# Drinks_MotorDriver-v0_2.net
KiCad netlist of a schematic drawn in EAGLE
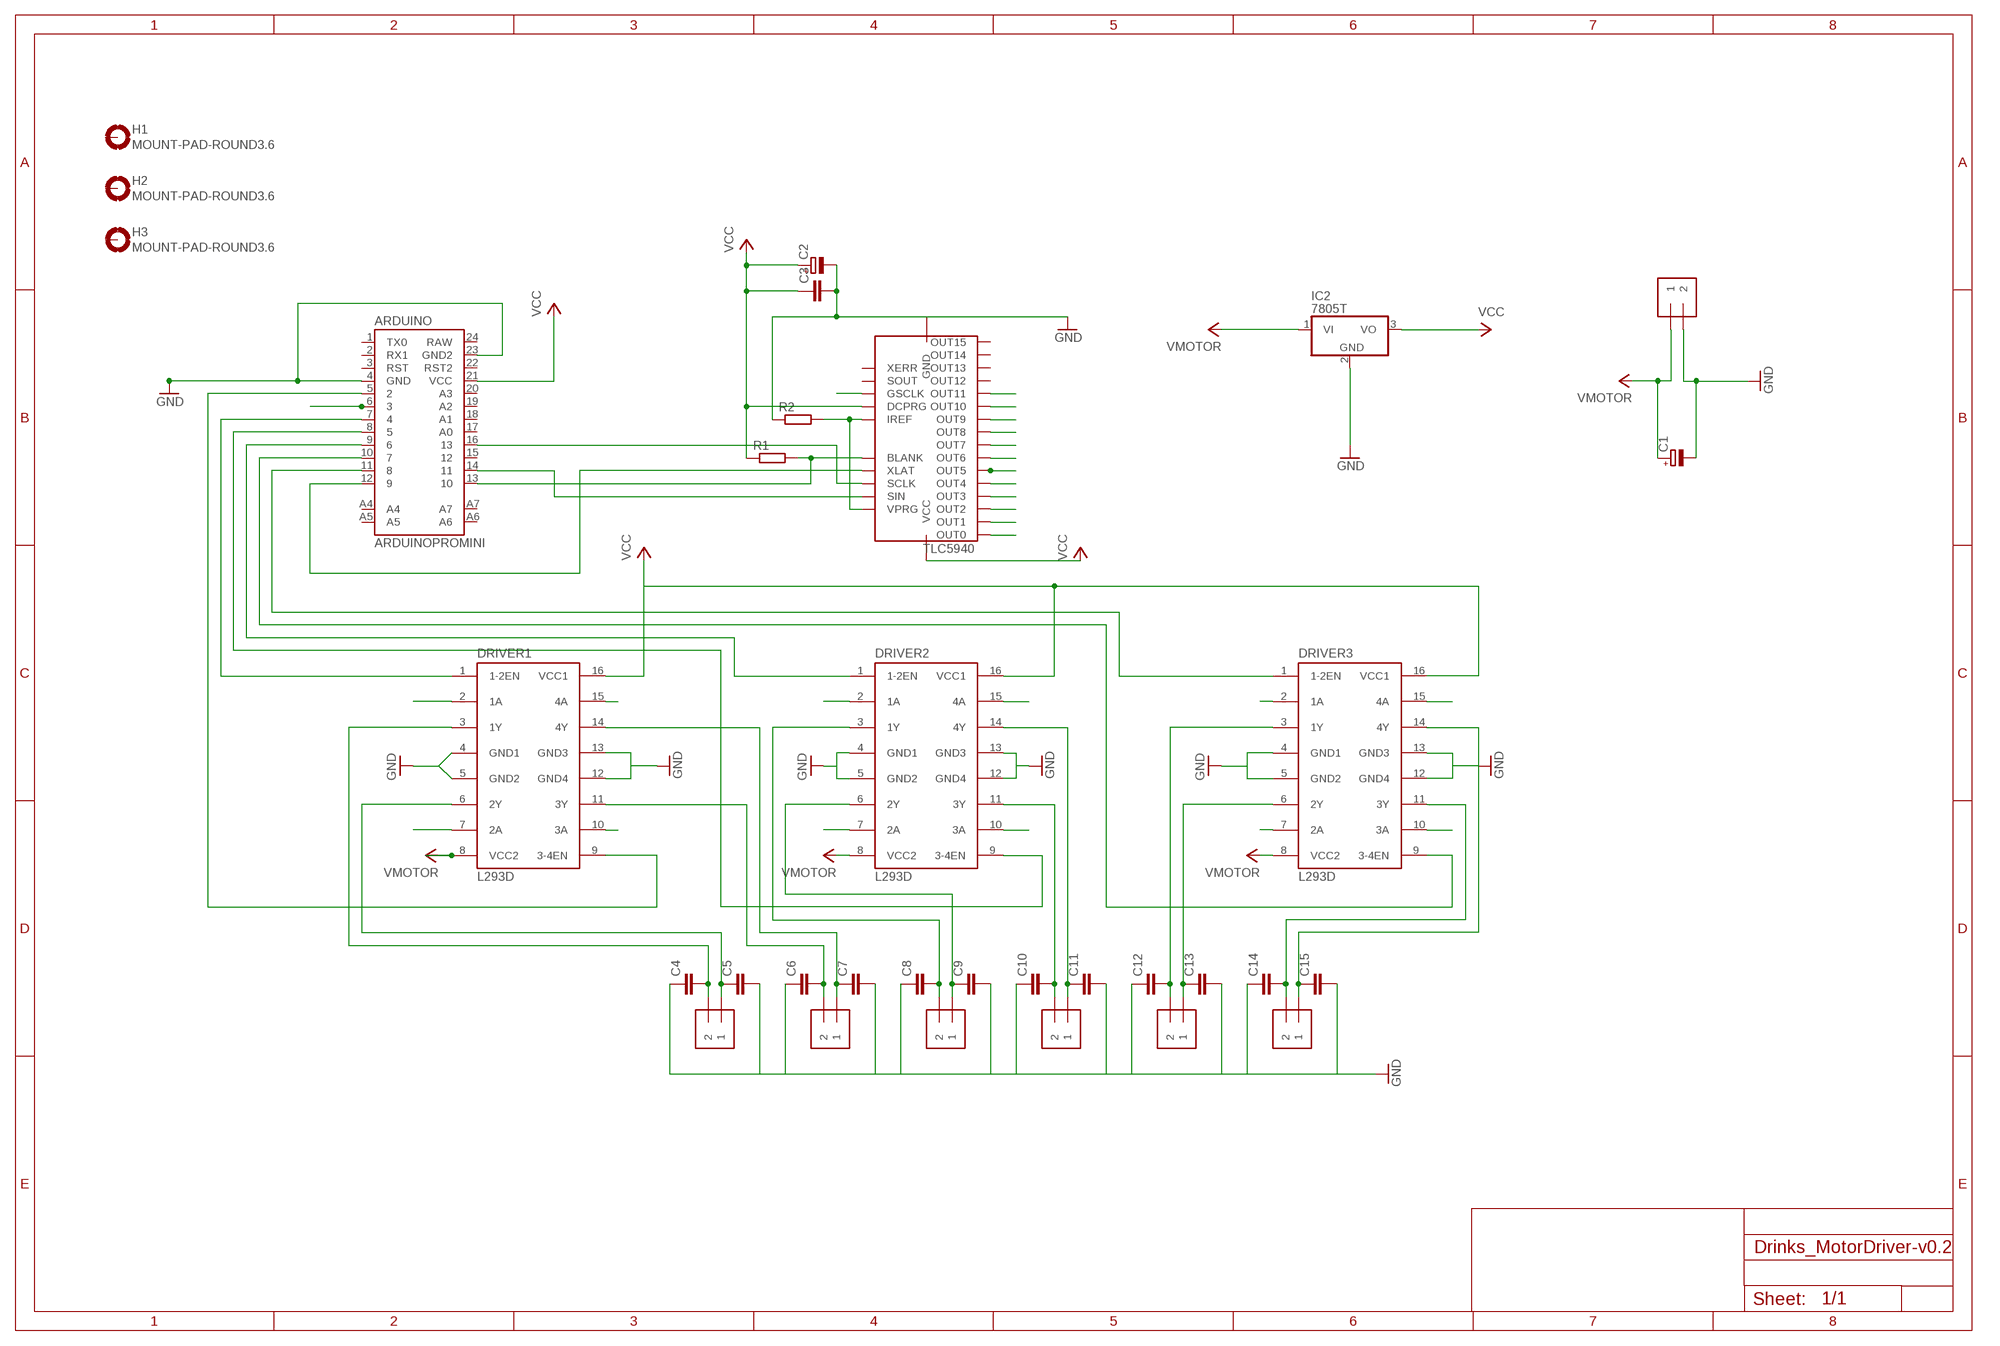
[diagram p0: schematic, sheet 1]

(export (version "E")
  (design (tool "Eeschema 10.0.6"))
  (components
    (comp (ref "ARDUINO")
      (value "ARDUINOPROMINI")
      (footprint "eagle-import:ARDUINO_PRO_MINI")
      (libsource (lib "eagle-import") (part "ARDUINO_PRO_MINI"))
    )
    (comp (ref "C1")
      (value "CPOL-EUE5-8.5")
      (footprint "eagle-import:E5-8,5")
      (libsource (lib "eagle-import") (part "CPOL-EUE5-8.5"))
    )
    (comp (ref "C2")
      (value "CPOL-EUE5-8.5")
      (footprint "eagle-import:E5-8,5")
      (libsource (lib "eagle-import") (part "CPOL-EUE5-8.5"))
    )
    (comp (ref "C3")
      (value "C-EU025-025X050")
      (footprint "eagle-import:C025-025X050")
      (libsource (lib "eagle-import") (part "C-EU025-025X050"))
    )
    (comp (ref "C4")
      (value "C-EU025-025X050")
      (footprint "eagle-import:C025-025X050")
      (libsource (lib "eagle-import") (part "C-EU025-025X050"))
    )
    (comp (ref "C5")
      (value "C-EU025-025X050")
      (footprint "eagle-import:C025-025X050")
      (libsource (lib "eagle-import") (part "C-EU025-025X050"))
    )
    (comp (ref "C6")
      (value "C-EU025-025X050")
      (footprint "eagle-import:C025-025X050")
      (libsource (lib "eagle-import") (part "C-EU025-025X050"))
    )
    (comp (ref "C7")
      (value "C-EU025-025X050")
      (footprint "eagle-import:C025-025X050")
      (libsource (lib "eagle-import") (part "C-EU025-025X050"))
    )
    (comp (ref "C8")
      (value "C-EU025-025X050")
      (footprint "eagle-import:C025-025X050")
      (libsource (lib "eagle-import") (part "C-EU025-025X050"))
    )
    (comp (ref "C9")
      (value "C-EU025-025X050")
      (footprint "eagle-import:C025-025X050")
      (libsource (lib "eagle-import") (part "C-EU025-025X050"))
    )
    (comp (ref "C10")
      (value "C-EU025-025X050")
      (footprint "eagle-import:C025-025X050")
      (libsource (lib "eagle-import") (part "C-EU025-025X050"))
    )
    (comp (ref "C11")
      (value "C-EU025-025X050")
      (footprint "eagle-import:C025-025X050")
      (libsource (lib "eagle-import") (part "C-EU025-025X050"))
    )
    (comp (ref "C12")
      (value "C-EU025-025X050")
      (footprint "eagle-import:C025-025X050")
      (libsource (lib "eagle-import") (part "C-EU025-025X050"))
    )
    (comp (ref "C13")
      (value "C-EU025-025X050")
      (footprint "eagle-import:C025-025X050")
      (libsource (lib "eagle-import") (part "C-EU025-025X050"))
    )
    (comp (ref "C14")
      (value "C-EU025-025X050")
      (footprint "eagle-import:C025-025X050")
      (libsource (lib "eagle-import") (part "C-EU025-025X050"))
    )
    (comp (ref "C15")
      (value "C-EU025-025X050")
      (footprint "eagle-import:C025-025X050")
      (libsource (lib "eagle-import") (part "C-EU025-025X050"))
    )
    (comp (ref "DRIVER1")
      (value "L293D")
      (footprint "eagle-import:DIL16")
      (libsource (lib "eagle-import") (part "L293D"))
    )
    (comp (ref "DRIVER2")
      (value "L293D")
      (footprint "eagle-import:DIL16")
      (libsource (lib "eagle-import") (part "L293D"))
    )
    (comp (ref "DRIVER3")
      (value "L293D")
      (footprint "eagle-import:DIL16")
      (libsource (lib "eagle-import") (part "L293D"))
    )
    (comp (ref "H1")
      (value "MOUNT-PAD-ROUND3.6")
      (footprint "eagle-import:3,6-PAD")
      (libsource (lib "eagle-import") (part "MOUNT-PAD-ROUND3.6"))
    )
    (comp (ref "H2")
      (value "MOUNT-PAD-ROUND3.6")
      (footprint "eagle-import:3,6-PAD")
      (libsource (lib "eagle-import") (part "MOUNT-PAD-ROUND3.6"))
    )
    (comp (ref "H3")
      (value "MOUNT-PAD-ROUND3.6")
      (footprint "eagle-import:3,6-PAD")
      (libsource (lib "eagle-import") (part "MOUNT-PAD-ROUND3.6"))
    )
    (comp (ref "IC2")
      (value "7805T")
      (footprint "eagle-import:TO220H")
      (libsource (lib "eagle-import") (part "78T05"))
    )
    (comp (ref "MOT1")
      (value "1X2-3.5MM")
      (footprint "eagle-import:1X2-3.5MM")
      (libsource (lib "eagle-import") (part "1X2-3.5MM"))
    )
    (comp (ref "MOT2")
      (value "1X2-3.5MM")
      (footprint "eagle-import:1X2-3.5MM")
      (libsource (lib "eagle-import") (part "1X2-3.5MM"))
    )
    (comp (ref "MOT3")
      (value "1X2-3.5MM")
      (footprint "eagle-import:1X2-3.5MM")
      (libsource (lib "eagle-import") (part "1X2-3.5MM"))
    )
    (comp (ref "MOT4")
      (value "1X2-3.5MM")
      (footprint "eagle-import:1X2-3.5MM")
      (libsource (lib "eagle-import") (part "1X2-3.5MM"))
    )
    (comp (ref "MOT5")
      (value "1X2-3.5MM")
      (footprint "eagle-import:1X2-3.5MM")
      (libsource (lib "eagle-import") (part "1X2-3.5MM"))
    )
    (comp (ref "MOT6")
      (value "1X2-3.5MM")
      (footprint "eagle-import:1X2-3.5MM")
      (libsource (lib "eagle-import") (part "1X2-3.5MM"))
    )
    (comp (ref "R1")
      (value "R-EU_0204/7")
      (footprint "eagle-import:0204_7")
      (libsource (lib "eagle-import") (part "R-EU_0204/7"))
    )
    (comp (ref "R2")
      (value "R-EU_0204/7")
      (footprint "eagle-import:0204_7")
      (libsource (lib "eagle-import") (part "R-EU_0204/7"))
    )
    (comp (ref "TLC5940")
      (value "IC-PACKAGE_DIL28-4")
      (footprint "eagle-import:IC-PACKAGE_DIL28-4")
      (libsource (lib "eagle-import") (part "IC-PACKAGE_DIL28-4"))
    )
    (comp (ref "VIN")
      (value "1X2-3.5MM")
      (footprint "eagle-import:1X2-3.5MM")
      (libsource (lib "eagle-import") (part "1X2-3.5MM"))
    )
  )
  (nets
    (net (code "1") (name "/GSCLK") (class "Default")
      (node (ref "ARDUINO") (pin "6") (pinfunction "3_6") (pintype "bidirectional"))
      (node (ref "TLC5940") (pin "18") (pinfunction "GSCLK_18") (pintype "input"))
    )
    (net (code "2") (name "/MOT1A") (class "Default")
      (node (ref "DRIVER1") (pin "2") (pinfunction "1A_2") (pintype "input"))
      (node (ref "TLC5940") (pin "28") (pinfunction "OUT0_28") (pintype "open_collector"))
    )
    (net (code "3") (name "/MOT1B") (class "Default")
      (node (ref "DRIVER1") (pin "7") (pinfunction "2A_7") (pintype "input"))
      (node (ref "TLC5940") (pin "1") (pinfunction "OUT1_1") (pintype "open_collector"))
    )
    (net (code "4") (name "/MOT2A") (class "Default")
      (node (ref "DRIVER1") (pin "10") (pinfunction "3A_10") (pintype "input"))
      (node (ref "TLC5940") (pin "2") (pinfunction "OUT2_2") (pintype "open_collector"))
    )
    (net (code "5") (name "/MOT2B") (class "Default")
      (node (ref "DRIVER1") (pin "15") (pinfunction "4A_15") (pintype "input"))
      (node (ref "TLC5940") (pin "3") (pinfunction "OUT3_3") (pintype "open_collector"))
    )
    (net (code "6") (name "/MOT3A") (class "Default")
      (node (ref "DRIVER2") (pin "2") (pinfunction "1A_2") (pintype "input"))
      (node (ref "TLC5940") (pin "4") (pinfunction "OUT4_4") (pintype "open_collector"))
    )
    (net (code "7") (name "/MOT3B") (class "Default")
      (node (ref "DRIVER2") (pin "7") (pinfunction "2A_7") (pintype "input"))
      (node (ref "TLC5940") (pin "5") (pinfunction "OUT5_5") (pintype "open_collector"))
    )
    (net (code "8") (name "/MOT4A") (class "Default")
      (node (ref "DRIVER2") (pin "10") (pinfunction "3A_10") (pintype "input"))
      (node (ref "TLC5940") (pin "6") (pinfunction "OUT6_6") (pintype "open_collector"))
    )
    (net (code "9") (name "/MOT4B") (class "Default")
      (node (ref "DRIVER2") (pin "15") (pinfunction "4A_15") (pintype "input"))
      (node (ref "TLC5940") (pin "7") (pinfunction "OUT7_7") (pintype "open_collector"))
    )
    (net (code "10") (name "/MOT5A") (class "Default")
      (node (ref "DRIVER3") (pin "2") (pinfunction "1A_2") (pintype "input"))
      (node (ref "TLC5940") (pin "8") (pinfunction "OUT8_8") (pintype "open_collector"))
    )
    (net (code "11") (name "/MOT5B") (class "Default")
      (node (ref "DRIVER3") (pin "7") (pinfunction "2A_7") (pintype "input"))
      (node (ref "TLC5940") (pin "9") (pinfunction "OUT9_9") (pintype "open_collector"))
    )
    (net (code "12") (name "/MOT6A") (class "Default")
      (node (ref "DRIVER3") (pin "10") (pinfunction "3A_10") (pintype "input"))
      (node (ref "TLC5940") (pin "10") (pinfunction "OUT10_10") (pintype "open_collector"))
    )
    (net (code "13") (name "/MOT6B") (class "Default")
      (node (ref "DRIVER3") (pin "15") (pinfunction "4A_15") (pintype "input"))
      (node (ref "TLC5940") (pin "11") (pinfunction "OUT11_11") (pintype "open_collector"))
    )
    (net (code "14") (name "GND") (class "Default")
      (node (ref "ARDUINO") (pin "23") (pinfunction "GND2_23") (pintype "bidirectional"))
      (node (ref "ARDUINO") (pin "4") (pinfunction "GND_4") (pintype "bidirectional"))
      (node (ref "C1") (pin "-") (pinfunction "-_-") (pintype "passive"))
      (node (ref "C10") (pin "1") (pinfunction "1_1") (pintype "passive"))
      (node (ref "C11") (pin "2") (pinfunction "2_2") (pintype "passive"))
      (node (ref "C12") (pin "1") (pinfunction "1_1") (pintype "passive"))
      (node (ref "C13") (pin "2") (pinfunction "2_2") (pintype "passive"))
      (node (ref "C14") (pin "1") (pinfunction "1_1") (pintype "passive"))
      (node (ref "C15") (pin "2") (pinfunction "2_2") (pintype "passive"))
      (node (ref "C2") (pin "-") (pinfunction "-_-") (pintype "passive"))
      (node (ref "C3") (pin "2") (pinfunction "2_2") (pintype "passive"))
      (node (ref "C4") (pin "1") (pinfunction "1_1") (pintype "passive"))
      (node (ref "C5") (pin "2") (pinfunction "2_2") (pintype "passive"))
      (node (ref "C6") (pin "1") (pinfunction "1_1") (pintype "passive"))
      (node (ref "C7") (pin "2") (pinfunction "2_2") (pintype "passive"))
      (node (ref "C8") (pin "1") (pinfunction "1_1") (pintype "passive"))
      (node (ref "C9") (pin "2") (pinfunction "2_2") (pintype "passive"))
      (node (ref "DRIVER1") (pin "12") (pinfunction "GND4_12") (pintype "power_in"))
      (node (ref "DRIVER1") (pin "13") (pinfunction "GND3_13") (pintype "power_in"))
      (node (ref "DRIVER1") (pin "4") (pinfunction "GND1_4") (pintype "power_in"))
      (node (ref "DRIVER1") (pin "5") (pinfunction "GND2_5") (pintype "power_in"))
      (node (ref "DRIVER2") (pin "12") (pinfunction "GND4_12") (pintype "power_in"))
      (node (ref "DRIVER2") (pin "13") (pinfunction "GND3_13") (pintype "power_in"))
      (node (ref "DRIVER2") (pin "4") (pinfunction "GND1_4") (pintype "power_in"))
      (node (ref "DRIVER2") (pin "5") (pinfunction "GND2_5") (pintype "power_in"))
      (node (ref "DRIVER3") (pin "12") (pinfunction "GND4_12") (pintype "power_in"))
      (node (ref "DRIVER3") (pin "13") (pinfunction "GND3_13") (pintype "power_in"))
      (node (ref "DRIVER3") (pin "4") (pinfunction "GND1_4") (pintype "power_in"))
      (node (ref "DRIVER3") (pin "5") (pinfunction "GND2_5") (pintype "power_in"))
      (node (ref "IC2") (pin "2") (pinfunction "GND_2") (pintype "passive"))
      (node (ref "R2") (pin "1") (pinfunction "1_1") (pintype "passive"))
      (node (ref "TLC5940") (pin "22") (pinfunction "GND_22") (pintype "power_in"))
      (node (ref "VIN") (pin "2") (pinfunction "2_2") (pintype "passive"))
    )
    (net (code "15") (name "Net-(ARDUINO-2)") (class "Default")
      (node (ref "ARDUINO") (pin "5") (pinfunction "2_5") (pintype "bidirectional"))
      (node (ref "DRIVER1") (pin "9") (pinfunction "3-4EN_9") (pintype "input"))
    )
    (net (code "16") (name "Net-(ARDUINO-4)") (class "Default")
      (node (ref "ARDUINO") (pin "7") (pinfunction "4_7") (pintype "bidirectional"))
      (node (ref "DRIVER1") (pin "1") (pinfunction "1-2EN_1") (pintype "input"))
    )
    (net (code "17") (name "Net-(ARDUINO-5)") (class "Default")
      (node (ref "ARDUINO") (pin "8") (pinfunction "5_8") (pintype "bidirectional"))
      (node (ref "DRIVER2") (pin "9") (pinfunction "3-4EN_9") (pintype "input"))
    )
    (net (code "18") (name "Net-(ARDUINO-6)") (class "Default")
      (node (ref "ARDUINO") (pin "9") (pinfunction "6_9") (pintype "bidirectional"))
      (node (ref "DRIVER2") (pin "1") (pinfunction "1-2EN_1") (pintype "input"))
    )
    (net (code "19") (name "Net-(ARDUINO-7)") (class "Default")
      (node (ref "ARDUINO") (pin "10") (pinfunction "7_10") (pintype "bidirectional"))
      (node (ref "DRIVER3") (pin "9") (pinfunction "3-4EN_9") (pintype "input"))
    )
    (net (code "20") (name "Net-(ARDUINO-8)") (class "Default")
      (node (ref "ARDUINO") (pin "11") (pinfunction "8_11") (pintype "bidirectional"))
      (node (ref "DRIVER3") (pin "1") (pinfunction "1-2EN_1") (pintype "input"))
    )
    (net (code "21") (name "Net-(ARDUINO-9)") (class "Default")
      (node (ref "ARDUINO") (pin "12") (pinfunction "9_12") (pintype "bidirectional"))
      (node (ref "TLC5940") (pin "24") (pinfunction "XLAT_24") (pintype "input"))
    )
    (net (code "22") (name "Net-(ARDUINO-10)") (class "Default")
      (node (ref "ARDUINO") (pin "13") (pinfunction "10_13") (pintype "bidirectional"))
      (node (ref "R1") (pin "2") (pinfunction "2_2") (pintype "passive"))
      (node (ref "TLC5940") (pin "23") (pinfunction "BLANK_23") (pintype "input"))
    )
    (net (code "23") (name "Net-(ARDUINO-11)") (class "Default")
      (node (ref "ARDUINO") (pin "14") (pinfunction "11_14") (pintype "bidirectional"))
      (node (ref "TLC5940") (pin "26") (pinfunction "SIN_26") (pintype "input"))
    )
    (net (code "24") (name "Net-(ARDUINO-13)") (class "Default")
      (node (ref "ARDUINO") (pin "16") (pinfunction "13_16") (pintype "bidirectional"))
      (node (ref "TLC5940") (pin "25") (pinfunction "SCLK_25") (pintype "input"))
    )
    (net (code "25") (name "Net-(DRIVER1-1Y)") (class "Default")
      (node (ref "C4") (pin "2") (pinfunction "2_2") (pintype "passive"))
      (node (ref "DRIVER1") (pin "3") (pinfunction "1Y_3") (pintype "output"))
      (node (ref "MOT1") (pin "2") (pinfunction "2_2") (pintype "passive"))
    )
    (net (code "26") (name "Net-(DRIVER1-2Y)") (class "Default")
      (node (ref "C5") (pin "1") (pinfunction "1_1") (pintype "passive"))
      (node (ref "DRIVER1") (pin "6") (pinfunction "2Y_6") (pintype "output"))
      (node (ref "MOT1") (pin "1") (pinfunction "1_1") (pintype "passive"))
    )
    (net (code "27") (name "Net-(DRIVER1-3Y)") (class "Default")
      (node (ref "C6") (pin "2") (pinfunction "2_2") (pintype "passive"))
      (node (ref "DRIVER1") (pin "11") (pinfunction "3Y_11") (pintype "output"))
      (node (ref "MOT2") (pin "2") (pinfunction "2_2") (pintype "passive"))
    )
    (net (code "28") (name "Net-(DRIVER1-4Y)") (class "Default")
      (node (ref "C7") (pin "1") (pinfunction "1_1") (pintype "passive"))
      (node (ref "DRIVER1") (pin "14") (pinfunction "4Y_14") (pintype "output"))
      (node (ref "MOT2") (pin "1") (pinfunction "1_1") (pintype "passive"))
    )
    (net (code "29") (name "Net-(DRIVER2-1Y)") (class "Default")
      (node (ref "C8") (pin "2") (pinfunction "2_2") (pintype "passive"))
      (node (ref "DRIVER2") (pin "3") (pinfunction "1Y_3") (pintype "output"))
      (node (ref "MOT3") (pin "2") (pinfunction "2_2") (pintype "passive"))
    )
    (net (code "30") (name "Net-(DRIVER2-2Y)") (class "Default")
      (node (ref "C9") (pin "1") (pinfunction "1_1") (pintype "passive"))
      (node (ref "DRIVER2") (pin "6") (pinfunction "2Y_6") (pintype "output"))
      (node (ref "MOT3") (pin "1") (pinfunction "1_1") (pintype "passive"))
    )
    (net (code "31") (name "Net-(DRIVER2-3Y)") (class "Default")
      (node (ref "C10") (pin "2") (pinfunction "2_2") (pintype "passive"))
      (node (ref "DRIVER2") (pin "11") (pinfunction "3Y_11") (pintype "output"))
      (node (ref "MOT4") (pin "2") (pinfunction "2_2") (pintype "passive"))
    )
    (net (code "32") (name "Net-(DRIVER2-4Y)") (class "Default")
      (node (ref "C11") (pin "1") (pinfunction "1_1") (pintype "passive"))
      (node (ref "DRIVER2") (pin "14") (pinfunction "4Y_14") (pintype "output"))
      (node (ref "MOT4") (pin "1") (pinfunction "1_1") (pintype "passive"))
    )
    (net (code "33") (name "Net-(DRIVER3-1Y)") (class "Default")
      (node (ref "C12") (pin "2") (pinfunction "2_2") (pintype "passive"))
      (node (ref "DRIVER3") (pin "3") (pinfunction "1Y_3") (pintype "output"))
      (node (ref "MOT5") (pin "2") (pinfunction "2_2") (pintype "passive"))
    )
    (net (code "34") (name "Net-(DRIVER3-2Y)") (class "Default")
      (node (ref "C13") (pin "1") (pinfunction "1_1") (pintype "passive"))
      (node (ref "DRIVER3") (pin "6") (pinfunction "2Y_6") (pintype "output"))
      (node (ref "MOT5") (pin "1") (pinfunction "1_1") (pintype "passive"))
    )
    (net (code "35") (name "Net-(DRIVER3-3Y)") (class "Default")
      (node (ref "C14") (pin "2") (pinfunction "2_2") (pintype "passive"))
      (node (ref "DRIVER3") (pin "11") (pinfunction "3Y_11") (pintype "output"))
      (node (ref "MOT6") (pin "2") (pinfunction "2_2") (pintype "passive"))
    )
    (net (code "36") (name "Net-(DRIVER3-4Y)") (class "Default")
      (node (ref "C15") (pin "1") (pinfunction "1_1") (pintype "passive"))
      (node (ref "DRIVER3") (pin "14") (pinfunction "4Y_14") (pintype "output"))
      (node (ref "MOT6") (pin "1") (pinfunction "1_1") (pintype "passive"))
    )
    (net (code "37") (name "Net-(TLC5940-IREF)") (class "Default")
      (node (ref "R2") (pin "2") (pinfunction "2_2") (pintype "passive"))
      (node (ref "TLC5940") (pin "20") (pinfunction "IREF_20") (pintype "passive"))
      (node (ref "TLC5940") (pin "27") (pinfunction "VPRG_27") (pintype "input"))
    )
    (net (code "38") (name "VCC") (class "Default")
      (node (ref "ARDUINO") (pin "21") (pinfunction "VCC_21") (pintype "bidirectional"))
      (node (ref "C2") (pin "+") (pinfunction "+_+") (pintype "passive"))
      (node (ref "C3") (pin "1") (pinfunction "1_1") (pintype "passive"))
      (node (ref "DRIVER1") (pin "16") (pinfunction "VCC1_16") (pintype "power_in"))
      (node (ref "DRIVER2") (pin "16") (pinfunction "VCC1_16") (pintype "power_in"))
      (node (ref "DRIVER3") (pin "16") (pinfunction "VCC1_16") (pintype "power_in"))
      (node (ref "IC2") (pin "3") (pinfunction "VO_3") (pintype "passive"))
      (node (ref "R1") (pin "1") (pinfunction "1_1") (pintype "passive"))
      (node (ref "TLC5940") (pin "19") (pinfunction "DCPRG_19") (pintype "input"))
      (node (ref "TLC5940") (pin "21") (pinfunction "VCC_21") (pintype "power_in"))
    )
    (net (code "39") (name "VMOTOR") (class "Default")
      (node (ref "C1") (pin "+") (pinfunction "+_+") (pintype "passive"))
      (node (ref "DRIVER1") (pin "8") (pinfunction "VCC2_8") (pintype "power_in"))
      (node (ref "DRIVER2") (pin "8") (pinfunction "VCC2_8") (pintype "power_in"))
      (node (ref "DRIVER3") (pin "8") (pinfunction "VCC2_8") (pintype "power_in"))
      (node (ref "IC2") (pin "1") (pinfunction "VI_1") (pintype "input"))
      (node (ref "VIN") (pin "1") (pinfunction "1_1") (pintype "passive"))
    )
    (net (code "40") (name "unconnected-(ARDUINO-12-Pad15)") (class "Default")
      (node (ref "ARDUINO") (pin "15") (pinfunction "12_15") (pintype "bidirectional"))
    )
    (net (code "41") (name "unconnected-(ARDUINO-A0-Pad17)") (class "Default")
      (node (ref "ARDUINO") (pin "17") (pinfunction "A0_17") (pintype "bidirectional"))
    )
    (net (code "42") (name "unconnected-(ARDUINO-A1-Pad18)") (class "Default")
      (node (ref "ARDUINO") (pin "18") (pinfunction "A1_18") (pintype "bidirectional"))
    )
    (net (code "43") (name "unconnected-(ARDUINO-A2-Pad19)") (class "Default")
      (node (ref "ARDUINO") (pin "19") (pinfunction "A2_19") (pintype "bidirectional"))
    )
    (net (code "44") (name "unconnected-(ARDUINO-A3-Pad20)") (class "Default")
      (node (ref "ARDUINO") (pin "20") (pinfunction "A3_20") (pintype "bidirectional"))
    )
    (net (code "45") (name "unconnected-(ARDUINO-PadA4)") (class "Default")
      (node (ref "ARDUINO") (pin "A4") (pinfunction "A4_A4") (pintype "bidirectional"))
    )
    (net (code "46") (name "unconnected-(ARDUINO-PadA5)") (class "Default")
      (node (ref "ARDUINO") (pin "A5") (pinfunction "A5_A5") (pintype "bidirectional"))
    )
    (net (code "47") (name "unconnected-(ARDUINO-PadA6)") (class "Default")
      (node (ref "ARDUINO") (pin "A6") (pinfunction "A6_A6") (pintype "bidirectional"))
    )
    (net (code "48") (name "unconnected-(ARDUINO-PadA7)") (class "Default")
      (node (ref "ARDUINO") (pin "A7") (pinfunction "A7_A7") (pintype "bidirectional"))
    )
    (net (code "49") (name "unconnected-(ARDUINO-RAW-Pad24)") (class "Default")
      (node (ref "ARDUINO") (pin "24") (pinfunction "RAW_24") (pintype "bidirectional"))
    )
    (net (code "50") (name "unconnected-(ARDUINO-RST-Pad3)") (class "Default")
      (node (ref "ARDUINO") (pin "3") (pinfunction "RST_3") (pintype "bidirectional"))
    )
    (net (code "51") (name "unconnected-(ARDUINO-RST2-Pad22)") (class "Default")
      (node (ref "ARDUINO") (pin "22") (pinfunction "RST2_22") (pintype "bidirectional"))
    )
    (net (code "52") (name "unconnected-(ARDUINO-RX1-Pad2)") (class "Default")
      (node (ref "ARDUINO") (pin "2") (pinfunction "RX1_2") (pintype "bidirectional"))
    )
    (net (code "53") (name "unconnected-(ARDUINO-TX0-Pad1)") (class "Default")
      (node (ref "ARDUINO") (pin "1") (pinfunction "TX0_1") (pintype "bidirectional"))
    )
    (net (code "54") (name "unconnected-(H1-MOUNT-PadB3,6)") (class "Default")
      (node (ref "H1") (pin "B3,6") (pinfunction "MOUNT_B3,6") (pintype "passive"))
    )
    (net (code "55") (name "unconnected-(H2-MOUNT-PadB3,6)") (class "Default")
      (node (ref "H2") (pin "B3,6") (pinfunction "MOUNT_B3,6") (pintype "passive"))
    )
    (net (code "56") (name "unconnected-(H3-MOUNT-PadB3,6)") (class "Default")
      (node (ref "H3") (pin "B3,6") (pinfunction "MOUNT_B3,6") (pintype "passive"))
    )
    (net (code "57") (name "unconnected-(TLC5940-OUT12-Pad12)") (class "Default")
      (node (ref "TLC5940") (pin "12") (pinfunction "OUT12_12") (pintype "open_collector"))
    )
    (net (code "58") (name "unconnected-(TLC5940-OUT13-Pad13)") (class "Default")
      (node (ref "TLC5940") (pin "13") (pinfunction "OUT13_13") (pintype "open_collector"))
    )
    (net (code "59") (name "unconnected-(TLC5940-OUT14-Pad14)") (class "Default")
      (node (ref "TLC5940") (pin "14") (pinfunction "OUT14_14") (pintype "open_collector"))
    )
    (net (code "60") (name "unconnected-(TLC5940-OUT15-Pad15)") (class "Default")
      (node (ref "TLC5940") (pin "15") (pinfunction "OUT15_15") (pintype "open_collector"))
    )
    (net (code "61") (name "unconnected-(TLC5940-SOUT-Pad17)") (class "Default")
      (node (ref "TLC5940") (pin "17") (pinfunction "SOUT_17") (pintype "output"))
    )
    (net (code "62") (name "unconnected-(TLC5940-XERR-Pad16)") (class "Default")
      (node (ref "TLC5940") (pin "16") (pinfunction "XERR_16") (pintype "open_collector"))
    )
  )
)
